# Module_Wi-Fi.net
KiCad netlist of a schematic drawn in Altium Designer
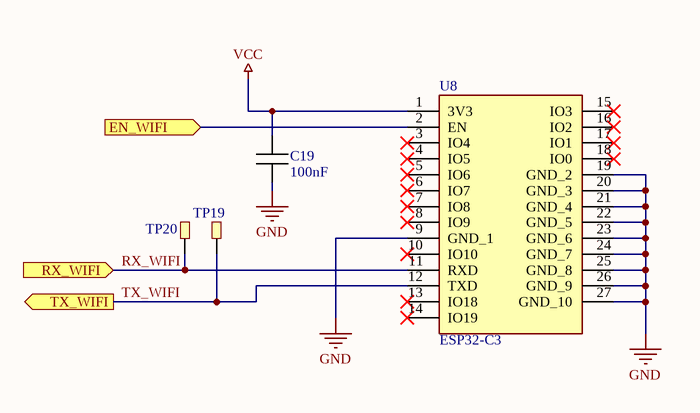
[diagram p0: Module_Wi-Fi.SchDoc]

(export (version "E")
  (design (tool "Eeschema 10.0.6"))
  (components
    (comp (ref "C19")
      (value "100nF")
      (footprint "CAPC1608X08M")
      (description "CAPC 100nF X7R 50V 10% 1608 (0603 INCH)")
      (fields (field (name "VOLTAGE") "50V") (field (name "MANUFACTURER") "TDK"))
      (libsource (lib "ETML-ES") (part "CAP"))
    )
    (comp (ref "TP19")
      (value "TestPoint")
      (footprint "KEYSTONE_5019")
      (libsource (lib "Schlib1") (part "TestPoint"))
    )
    (comp (ref "TP20")
      (value "TestPoint")
      (footprint "KEYSTONE_5019")
      (libsource (lib "Schlib1") (part "TestPoint"))
    )
    (comp (ref "U8") (value "ESP32-C3") (footprint "ESP32_C3") (libsource (lib "Schlib1") (part "ESP32-C3")))
  )
  (nets
    (net (code "1") (name "/EN_WIFI") (class "Default")
      (node (ref "U8") (pin "2") (pinfunction "EN_2") (pintype "passive"))
    )
    (net (code "2") (name "/RX_WIFI") (class "Default")
      (node (ref "TP20") (pin "1") (pinfunction "1_1") (pintype "passive"))
      (node (ref "U8") (pin "11") (pinfunction "RXD_11") (pintype "passive"))
    )
    (net (code "3") (name "/TX_WIFI") (class "Default")
      (node (ref "TP19") (pin "1") (pinfunction "1_1") (pintype "passive"))
      (node (ref "U8") (pin "12") (pinfunction "TXD_12") (pintype "passive"))
    )
    (net (code "4") (name "GND") (class "Default")
      (node (ref "C19") (pin "1") (pinfunction "1_1") (pintype "passive"))
      (node (ref "U8") (pin "19") (pinfunction "GND_2_19") (pintype "passive"))
      (node (ref "U8") (pin "20") (pinfunction "GND_3_20") (pintype "passive"))
      (node (ref "U8") (pin "21") (pinfunction "GND_4_21") (pintype "passive"))
      (node (ref "U8") (pin "22") (pinfunction "GND_5_22") (pintype "passive"))
      (node (ref "U8") (pin "23") (pinfunction "GND_6_23") (pintype "passive"))
      (node (ref "U8") (pin "24") (pinfunction "GND_7_24") (pintype "passive"))
      (node (ref "U8") (pin "25") (pinfunction "GND_8_25") (pintype "passive"))
      (node (ref "U8") (pin "26") (pinfunction "GND_9_26") (pintype "passive"))
      (node (ref "U8") (pin "27") (pinfunction "GND_10_27") (pintype "passive"))
      (node (ref "U8") (pin "9") (pinfunction "GND_1_9") (pintype "passive"))
    )
    (net (code "5") (name "VCC") (class "Default")
      (node (ref "C19") (pin "2") (pinfunction "2_2") (pintype "passive"))
      (node (ref "U8") (pin "1") (pinfunction "3V3_1") (pintype "passive"))
    )
    (net (code "6") (name "unconnected-(U8-IO0-Pad18)") (class "Default")
      (node (ref "U8") (pin "18") (pinfunction "IO0_18") (pintype "passive+no_connect"))
    )
    (net (code "7") (name "unconnected-(U8-IO1-Pad17)") (class "Default")
      (node (ref "U8") (pin "17") (pinfunction "IO1_17") (pintype "passive+no_connect"))
    )
    (net (code "8") (name "unconnected-(U8-IO2-Pad16)") (class "Default")
      (node (ref "U8") (pin "16") (pinfunction "IO2_16") (pintype "passive+no_connect"))
    )
    (net (code "9") (name "unconnected-(U8-IO3-Pad15)") (class "Default")
      (node (ref "U8") (pin "15") (pinfunction "IO3_15") (pintype "passive+no_connect"))
    )
    (net (code "10") (name "unconnected-(U8-IO4-Pad3)") (class "Default")
      (node (ref "U8") (pin "3") (pinfunction "IO4_3") (pintype "passive+no_connect"))
    )
    (net (code "11") (name "unconnected-(U8-IO5-Pad4)") (class "Default")
      (node (ref "U8") (pin "4") (pinfunction "IO5_4") (pintype "passive+no_connect"))
    )
    (net (code "12") (name "unconnected-(U8-IO6-Pad5)") (class "Default")
      (node (ref "U8") (pin "5") (pinfunction "IO6_5") (pintype "passive+no_connect"))
    )
    (net (code "13") (name "unconnected-(U8-IO7-Pad6)") (class "Default")
      (node (ref "U8") (pin "6") (pinfunction "IO7_6") (pintype "passive+no_connect"))
    )
    (net (code "14") (name "unconnected-(U8-IO8-Pad7)") (class "Default")
      (node (ref "U8") (pin "7") (pinfunction "IO8_7") (pintype "passive+no_connect"))
    )
    (net (code "15") (name "unconnected-(U8-IO9-Pad8)") (class "Default")
      (node (ref "U8") (pin "8") (pinfunction "IO9_8") (pintype "passive+no_connect"))
    )
    (net (code "16") (name "unconnected-(U8-IO10-Pad10)") (class "Default")
      (node (ref "U8") (pin "10") (pinfunction "IO10_10") (pintype "passive+no_connect"))
    )
    (net (code "17") (name "unconnected-(U8-IO18-Pad13)") (class "Default")
      (node (ref "U8") (pin "13") (pinfunction "IO18_13") (pintype "passive+no_connect"))
    )
    (net (code "18") (name "unconnected-(U8-IO19-Pad14)") (class "Default")
      (node (ref "U8") (pin "14") (pinfunction "IO19_14") (pintype "passive+no_connect"))
    )
  )
)
